# scheme_EasyEDA.net
KiCad netlist of a schematic drawn in EasyEDA
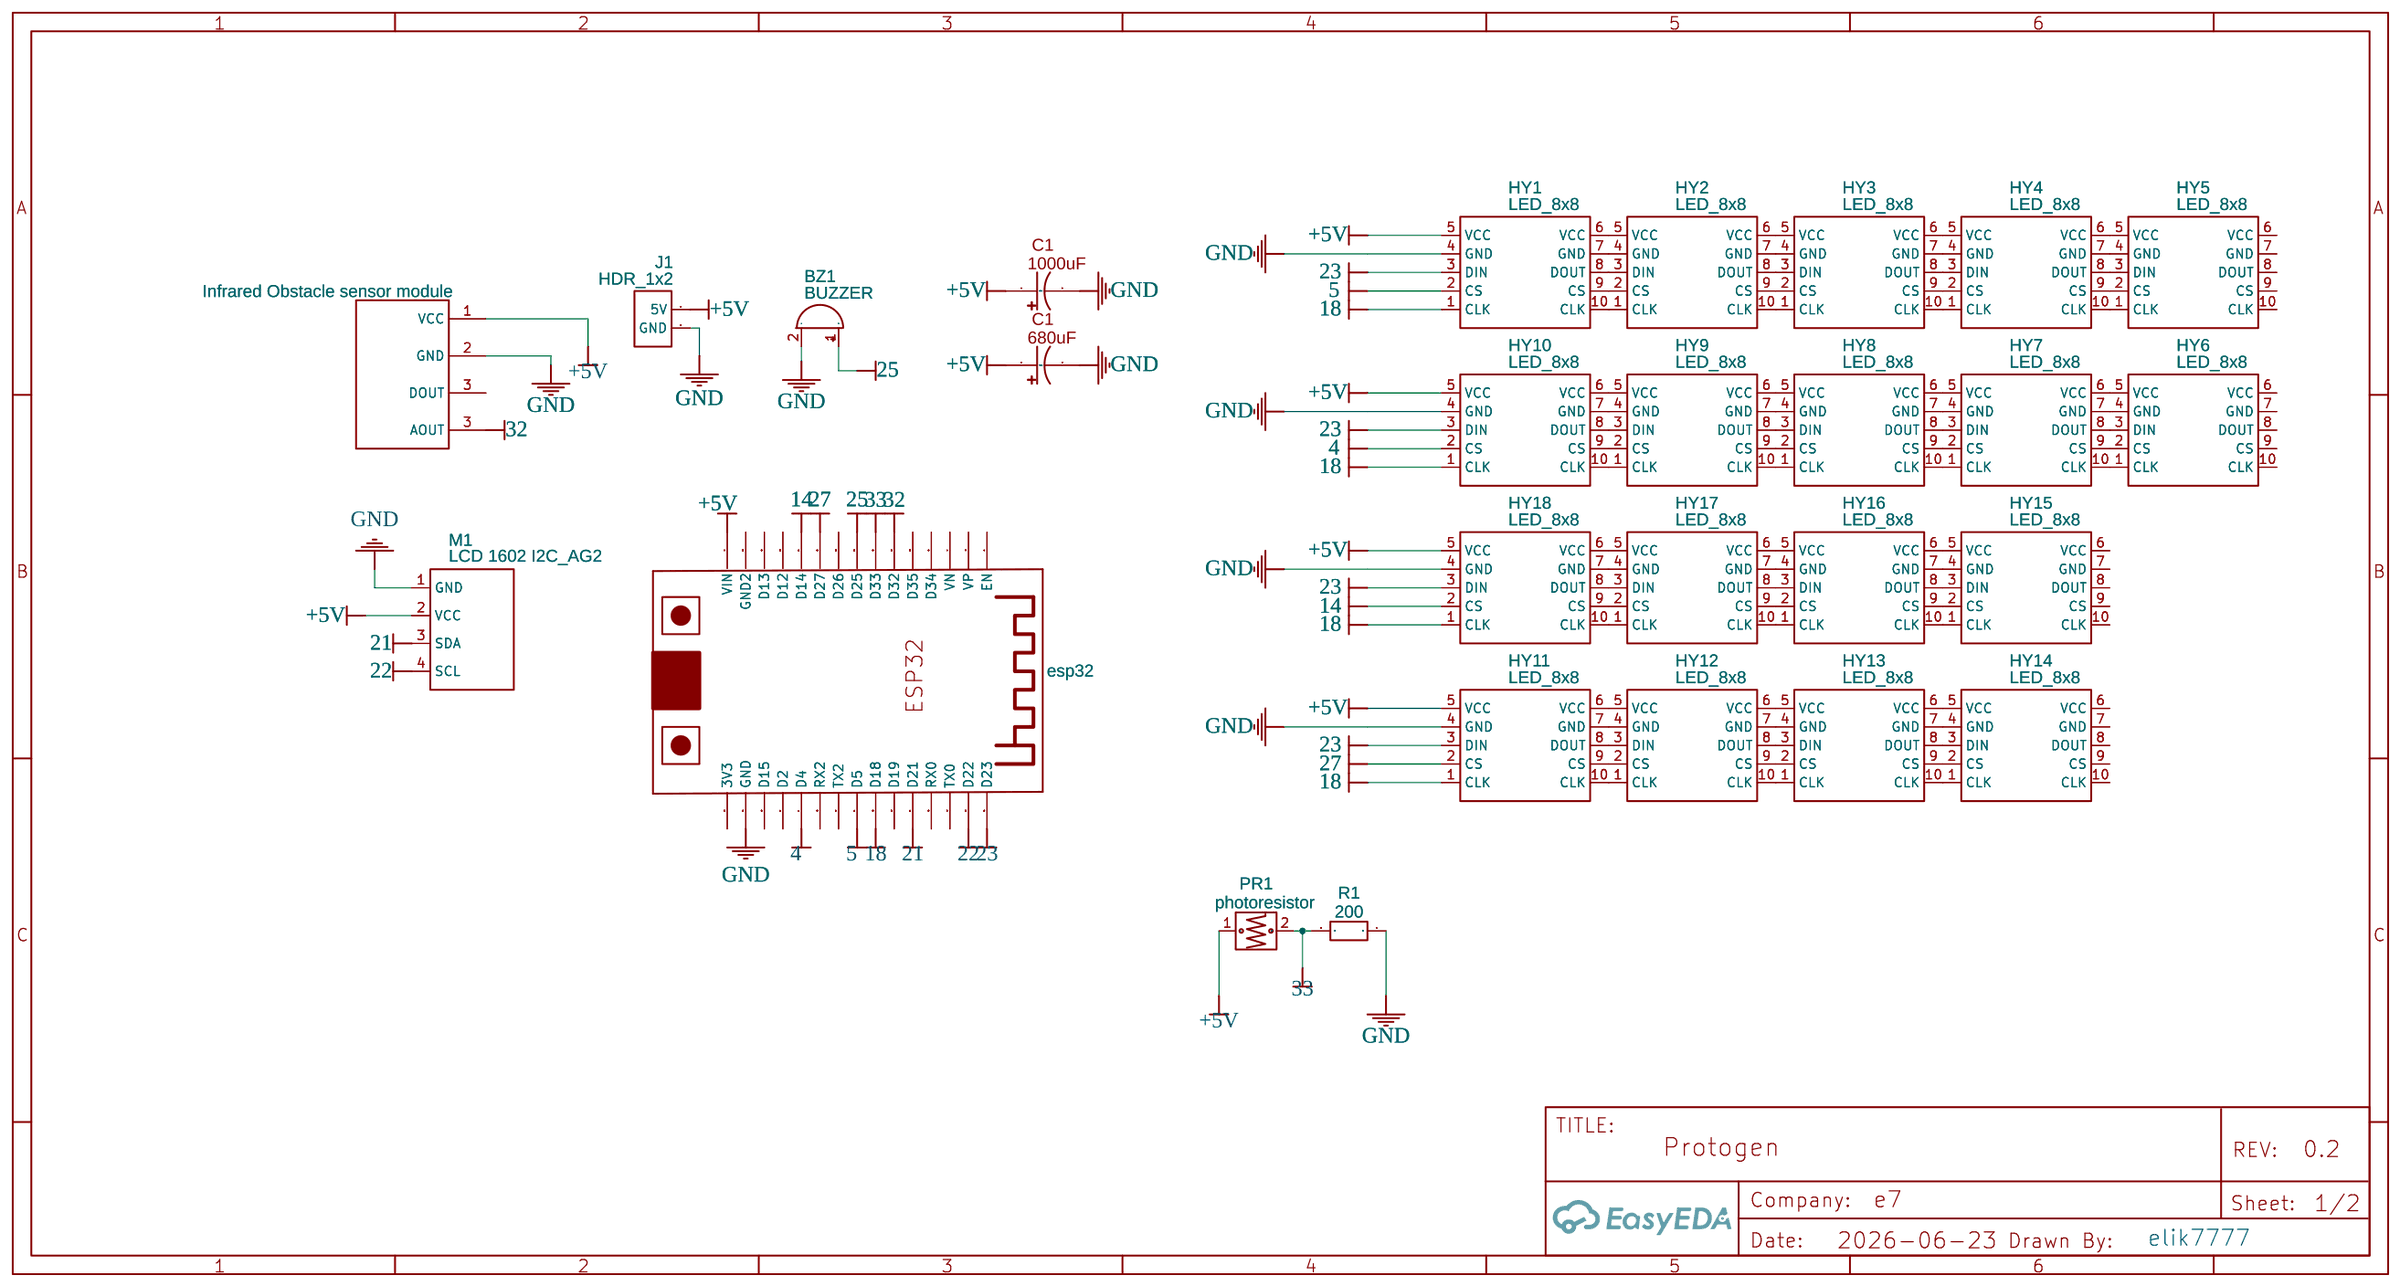
[diagram p0: schematic sheet]

(export (version "E")
  (design (tool "Eeschema 10.0.6"))
  (components
    (comp (ref "1") (value "esp32") (libsource (lib "") (part "ESP32-DEVKIT-V1-30PIN")))
    (comp (ref "BZ1") (value "BUZZER") (libsource (lib "") (part "DEVICE_BUZZER KU")))
    (comp (ref "HY1")
      (value "LED_8x8")
      (fields
        (field (name "Manufacturer Part") "32305941397 B")
        (field (name "Manufacturer") "Artillery 3C Store")
      )
      (libsource (lib "") (part "LED_8x8_MAX7219 cm"))
    )
    (comp (ref "HY2")
      (value "LED_8x8")
      (fields
        (field (name "Manufacturer Part") "32305941397 B")
        (field (name "Manufacturer") "Artillery 3C Store")
      )
      (libsource (lib "") (part "LED_8x8_MAX7219 cm"))
    )
    (comp (ref "HY3")
      (value "LED_8x8")
      (fields
        (field (name "Manufacturer Part") "32305941397 B")
        (field (name "Manufacturer") "Artillery 3C Store")
      )
      (libsource (lib "") (part "LED_8x8_MAX7219 cm"))
    )
    (comp (ref "HY4")
      (value "LED_8x8")
      (fields
        (field (name "Manufacturer Part") "32305941397 B")
        (field (name "Manufacturer") "Artillery 3C Store")
      )
      (libsource (lib "") (part "LED_8x8_MAX7219 cm"))
    )
    (comp (ref "HY5")
      (value "LED_8x8")
      (fields
        (field (name "Manufacturer Part") "32305941397 B")
        (field (name "Manufacturer") "Artillery 3C Store")
      )
      (libsource (lib "") (part "LED_8x8_MAX7219 cm"))
    )
    (comp (ref "HY6")
      (value "LED_8x8")
      (fields
        (field (name "Manufacturer Part") "32305941397 B")
        (field (name "Manufacturer") "Artillery 3C Store")
      )
      (libsource (lib "") (part "LED_8x8_MAX7219 cm"))
    )
    (comp (ref "HY7")
      (value "LED_8x8")
      (fields
        (field (name "Manufacturer Part") "32305941397 B")
        (field (name "Manufacturer") "Artillery 3C Store")
      )
      (libsource (lib "") (part "LED_8x8_MAX7219 cm"))
    )
    (comp (ref "HY8")
      (value "LED_8x8")
      (fields
        (field (name "Manufacturer Part") "32305941397 B")
        (field (name "Manufacturer") "Artillery 3C Store")
      )
      (libsource (lib "") (part "LED_8x8_MAX7219 cm"))
    )
    (comp (ref "HY9")
      (value "LED_8x8")
      (fields
        (field (name "Manufacturer Part") "32305941397 B")
        (field (name "Manufacturer") "Artillery 3C Store")
      )
      (libsource (lib "") (part "LED_8x8_MAX7219 cm"))
    )
    (comp (ref "HY10")
      (value "LED_8x8")
      (fields
        (field (name "Manufacturer Part") "32305941397 B")
        (field (name "Manufacturer") "Artillery 3C Store")
      )
      (libsource (lib "") (part "LED_8x8_MAX7219 cm"))
    )
    (comp (ref "HY11")
      (value "LED_8x8")
      (fields
        (field (name "Manufacturer Part") "32305941397 B")
        (field (name "Manufacturer") "Artillery 3C Store")
      )
      (libsource (lib "") (part "LED_8x8_MAX7219 cm"))
    )
    (comp (ref "HY12")
      (value "LED_8x8")
      (fields
        (field (name "Manufacturer Part") "32305941397 B")
        (field (name "Manufacturer") "Artillery 3C Store")
      )
      (libsource (lib "") (part "LED_8x8_MAX7219 cm"))
    )
    (comp (ref "HY13")
      (value "LED_8x8")
      (fields
        (field (name "Manufacturer Part") "32305941397 B")
        (field (name "Manufacturer") "Artillery 3C Store")
      )
      (libsource (lib "") (part "LED_8x8_MAX7219 cm"))
    )
    (comp (ref "HY14")
      (value "LED_8x8")
      (fields
        (field (name "Manufacturer Part") "32305941397 B")
        (field (name "Manufacturer") "Artillery 3C Store")
      )
      (libsource (lib "") (part "LED_8x8_MAX7219 cm"))
    )
    (comp (ref "HY15")
      (value "LED_8x8")
      (fields
        (field (name "Manufacturer Part") "32305941397 B")
        (field (name "Manufacturer") "Artillery 3C Store")
      )
      (libsource (lib "") (part "LED_8x8_MAX7219 cm"))
    )
    (comp (ref "HY16")
      (value "LED_8x8")
      (fields
        (field (name "Manufacturer Part") "32305941397 B")
        (field (name "Manufacturer") "Artillery 3C Store")
      )
      (libsource (lib "") (part "LED_8x8_MAX7219 cm"))
    )
    (comp (ref "HY17")
      (value "LED_8x8")
      (fields
        (field (name "Manufacturer Part") "32305941397 B")
        (field (name "Manufacturer") "Artillery 3C Store")
      )
      (libsource (lib "") (part "LED_8x8_MAX7219 cm"))
    )
    (comp (ref "HY18")
      (value "LED_8x8")
      (fields
        (field (name "Manufacturer Part") "32305941397 B")
        (field (name "Manufacturer") "Artillery 3C Store")
      )
      (libsource (lib "") (part "LED_8x8_MAX7219 cm"))
    )
    (comp (ref "J1") (value "HDR_1x2") (libsource (lib "") (part "HDR-M-2.54_1x2")))
    (comp (ref "M1") (value "LCD 1602 I2C_AG2") (libsource (lib "") (part "LCD 1602 I2C_AG2")))
    (comp (ref "PR1") (value "photoresistor") (libsource (lib "") (part "photoresistor")))
    (comp (ref "R1") (value "200") (libsource (lib "") (part "R_AXIAL-0.3_EU")))
    (comp (ref "U1") (value "CAPACITOR") (libsource (lib "") (part "CAPACITOR_1")))
    (comp (ref "U2") (value "CAPACITOR") (libsource (lib "") (part "CAPACITOR")))
    (comp (ref "U3")
      (value "Infrared Obstacle sensor module")
      (libsource (lib "") (part "Infrared Obstacle sensor module"))
    )
  )
  (nets
    (net (code "1") (name "+5V") (class "Default")
      (node (ref "1") (pin "VIN") (pinfunction "VIN_VIN") (pintype "unspecified"))
      (node (ref "HY1") (pin "5") (pinfunction "VCC_5") (pintype "unspecified"))
      (node (ref "HY10") (pin "5") (pinfunction "VCC_5") (pintype "unspecified"))
      (node (ref "HY11") (pin "5") (pinfunction "VCC_5") (pintype "unspecified"))
      (node (ref "HY18") (pin "5") (pinfunction "VCC_5") (pintype "unspecified"))
      (node (ref "J1") (pin "1") (pinfunction "5V_1") (pintype "unspecified"))
      (node (ref "M1") (pin "2") (pinfunction "VCC_2") (pintype "unspecified"))
      (node (ref "PR1") (pin "1") (pinfunction "1_1") (pintype "unspecified"))
      (node (ref "U1") (pin "1") (pinfunction "1_1") (pintype "unspecified"))
      (node (ref "U2") (pin "1") (pinfunction "1_1") (pintype "unspecified"))
      (node (ref "U3") (pin "1") (pinfunction "VCC_1") (pintype "unspecified"))
    )
    (net (code "2") (name "4") (class "Default")
      (node (ref "1") (pin "D4") (pinfunction "D4_D4") (pintype "unspecified"))
      (node (ref "HY10") (pin "2") (pinfunction "CS_2") (pintype "unspecified"))
    )
    (net (code "3") (name "5") (class "Default")
      (node (ref "1") (pin "D5") (pinfunction "D5_D5") (pintype "unspecified"))
      (node (ref "HY1") (pin "2") (pinfunction "CS_2") (pintype "unspecified"))
    )
    (net (code "4") (name "14") (class "Default")
      (node (ref "1") (pin "D14") (pinfunction "D14_D14") (pintype "unspecified"))
      (node (ref "HY18") (pin "2") (pinfunction "CS_2") (pintype "unspecified"))
    )
    (net (code "5") (name "18") (class "Default")
      (node (ref "1") (pin "D18") (pinfunction "D18_D18") (pintype "unspecified"))
      (node (ref "HY1") (pin "1") (pinfunction "CLK_1") (pintype "unspecified"))
      (node (ref "HY10") (pin "1") (pinfunction "CLK_1") (pintype "unspecified"))
      (node (ref "HY11") (pin "1") (pinfunction "CLK_1") (pintype "unspecified"))
      (node (ref "HY18") (pin "1") (pinfunction "CLK_1") (pintype "unspecified"))
    )
    (net (code "6") (name "21") (class "Default")
      (node (ref "1") (pin "D21") (pinfunction "D21_D21") (pintype "unspecified"))
      (node (ref "M1") (pin "3") (pinfunction "SDA_3") (pintype "unspecified"))
    )
    (net (code "7") (name "22") (class "Default")
      (node (ref "1") (pin "D22") (pinfunction "D22_D22") (pintype "unspecified"))
      (node (ref "M1") (pin "4") (pinfunction "SCL_4") (pintype "unspecified"))
    )
    (net (code "8") (name "23") (class "Default")
      (node (ref "1") (pin "D23") (pinfunction "D23_D23") (pintype "unspecified"))
      (node (ref "HY1") (pin "3") (pinfunction "DIN_3") (pintype "unspecified"))
      (node (ref "HY10") (pin "3") (pinfunction "DIN_3") (pintype "unspecified"))
      (node (ref "HY11") (pin "3") (pinfunction "DIN_3") (pintype "unspecified"))
      (node (ref "HY18") (pin "3") (pinfunction "DIN_3") (pintype "unspecified"))
    )
    (net (code "9") (name "25") (class "Default")
      (node (ref "1") (pin "D25") (pinfunction "D25_D25") (pintype "unspecified"))
      (node (ref "BZ1") (pin "1") (pinfunction "+_1") (pintype "unspecified"))
    )
    (net (code "10") (name "27") (class "Default")
      (node (ref "1") (pin "D27") (pinfunction "D27_D27") (pintype "unspecified"))
      (node (ref "HY11") (pin "2") (pinfunction "CS_2") (pintype "unspecified"))
    )
    (net (code "11") (name "32") (class "Default")
      (node (ref "1") (pin "D32") (pinfunction "D32_D32") (pintype "unspecified"))
      (node (ref "U3") (pin "3") (pinfunction "AOUT_3") (pintype "unspecified"))
    )
    (net (code "12") (name "33") (class "Default")
      (node (ref "1") (pin "D33") (pinfunction "D33_D33") (pintype "unspecified"))
      (node (ref "PR1") (pin "2") (pinfunction "2_2") (pintype "unspecified"))
      (node (ref "R1") (pin "2") (pinfunction "2_2") (pintype "unspecified"))
    )
    (net (code "13") (name "GND") (class "Default")
      (node (ref "1") (pin "GND") (pinfunction "GND_GND") (pintype "unspecified"))
      (node (ref "BZ1") (pin "2") (pinfunction "-_2") (pintype "unspecified"))
      (node (ref "HY1") (pin "4") (pinfunction "GND_4") (pintype "unspecified"))
      (node (ref "HY10") (pin "4") (pinfunction "GND_4") (pintype "unspecified"))
      (node (ref "HY11") (pin "4") (pinfunction "GND_4") (pintype "unspecified"))
      (node (ref "HY18") (pin "4") (pinfunction "GND_4") (pintype "unspecified"))
      (node (ref "J1") (pin "2") (pinfunction "GND_2") (pintype "unspecified"))
      (node (ref "M1") (pin "1") (pinfunction "GND_1") (pintype "unspecified"))
      (node (ref "R1") (pin "1") (pinfunction "1_1") (pintype "unspecified"))
      (node (ref "U1") (pin "2") (pinfunction "2_2") (pintype "unspecified"))
      (node (ref "U2") (pin "2") (pinfunction "2_2") (pintype "unspecified"))
      (node (ref "U3") (pin "2") (pinfunction "GND_2") (pintype "unspecified"))
    )
    (net (code "14") (name "Net-(HY1-CLK-Pad10)") (class "Default")
      (node (ref "HY1") (pin "10") (pinfunction "CLK_10") (pintype "unspecified"))
      (node (ref "HY2") (pin "1") (pinfunction "CLK_1") (pintype "unspecified"))
    )
    (net (code "15") (name "Net-(HY1-CS-Pad9)") (class "Default")
      (node (ref "HY1") (pin "9") (pinfunction "CS_9") (pintype "unspecified"))
      (node (ref "HY2") (pin "2") (pinfunction "CS_2") (pintype "unspecified"))
    )
    (net (code "16") (name "Net-(HY1-DOUT)") (class "Default")
      (node (ref "HY1") (pin "8") (pinfunction "DOUT_8") (pintype "unspecified"))
      (node (ref "HY2") (pin "3") (pinfunction "DIN_3") (pintype "unspecified"))
    )
    (net (code "17") (name "Net-(HY1-GND-Pad7)") (class "Default")
      (node (ref "HY1") (pin "7") (pinfunction "GND_7") (pintype "unspecified"))
      (node (ref "HY2") (pin "4") (pinfunction "GND_4") (pintype "unspecified"))
    )
    (net (code "18") (name "Net-(HY1-VCC-Pad6)") (class "Default")
      (node (ref "HY1") (pin "6") (pinfunction "VCC_6") (pintype "unspecified"))
      (node (ref "HY2") (pin "5") (pinfunction "VCC_5") (pintype "unspecified"))
    )
    (net (code "19") (name "Net-(HY2-CLK-Pad10)") (class "Default")
      (node (ref "HY2") (pin "10") (pinfunction "CLK_10") (pintype "unspecified"))
      (node (ref "HY3") (pin "1") (pinfunction "CLK_1") (pintype "unspecified"))
    )
    (net (code "20") (name "Net-(HY2-CS-Pad9)") (class "Default")
      (node (ref "HY2") (pin "9") (pinfunction "CS_9") (pintype "unspecified"))
      (node (ref "HY3") (pin "2") (pinfunction "CS_2") (pintype "unspecified"))
    )
    (net (code "21") (name "Net-(HY2-DOUT)") (class "Default")
      (node (ref "HY2") (pin "8") (pinfunction "DOUT_8") (pintype "unspecified"))
      (node (ref "HY3") (pin "3") (pinfunction "DIN_3") (pintype "unspecified"))
    )
    (net (code "22") (name "Net-(HY2-GND-Pad7)") (class "Default")
      (node (ref "HY2") (pin "7") (pinfunction "GND_7") (pintype "unspecified"))
      (node (ref "HY3") (pin "4") (pinfunction "GND_4") (pintype "unspecified"))
    )
    (net (code "23") (name "Net-(HY2-VCC-Pad6)") (class "Default")
      (node (ref "HY2") (pin "6") (pinfunction "VCC_6") (pintype "unspecified"))
      (node (ref "HY3") (pin "5") (pinfunction "VCC_5") (pintype "unspecified"))
    )
    (net (code "24") (name "Net-(HY3-CLK-Pad10)") (class "Default")
      (node (ref "HY3") (pin "10") (pinfunction "CLK_10") (pintype "unspecified"))
      (node (ref "HY4") (pin "1") (pinfunction "CLK_1") (pintype "unspecified"))
    )
    (net (code "25") (name "Net-(HY3-CS-Pad9)") (class "Default")
      (node (ref "HY3") (pin "9") (pinfunction "CS_9") (pintype "unspecified"))
      (node (ref "HY4") (pin "2") (pinfunction "CS_2") (pintype "unspecified"))
    )
    (net (code "26") (name "Net-(HY3-DOUT)") (class "Default")
      (node (ref "HY3") (pin "8") (pinfunction "DOUT_8") (pintype "unspecified"))
      (node (ref "HY4") (pin "3") (pinfunction "DIN_3") (pintype "unspecified"))
    )
    (net (code "27") (name "Net-(HY3-GND-Pad7)") (class "Default")
      (node (ref "HY3") (pin "7") (pinfunction "GND_7") (pintype "unspecified"))
      (node (ref "HY4") (pin "4") (pinfunction "GND_4") (pintype "unspecified"))
    )
    (net (code "28") (name "Net-(HY3-VCC-Pad6)") (class "Default")
      (node (ref "HY3") (pin "6") (pinfunction "VCC_6") (pintype "unspecified"))
      (node (ref "HY4") (pin "5") (pinfunction "VCC_5") (pintype "unspecified"))
    )
    (net (code "29") (name "Net-(HY4-CLK-Pad10)") (class "Default")
      (node (ref "HY4") (pin "10") (pinfunction "CLK_10") (pintype "unspecified"))
      (node (ref "HY5") (pin "1") (pinfunction "CLK_1") (pintype "unspecified"))
    )
    (net (code "30") (name "Net-(HY4-CS-Pad9)") (class "Default")
      (node (ref "HY4") (pin "9") (pinfunction "CS_9") (pintype "unspecified"))
      (node (ref "HY5") (pin "2") (pinfunction "CS_2") (pintype "unspecified"))
    )
    (net (code "31") (name "Net-(HY4-DOUT)") (class "Default")
      (node (ref "HY4") (pin "8") (pinfunction "DOUT_8") (pintype "unspecified"))
      (node (ref "HY5") (pin "3") (pinfunction "DIN_3") (pintype "unspecified"))
    )
    (net (code "32") (name "Net-(HY4-GND-Pad7)") (class "Default")
      (node (ref "HY4") (pin "7") (pinfunction "GND_7") (pintype "unspecified"))
      (node (ref "HY5") (pin "4") (pinfunction "GND_4") (pintype "unspecified"))
    )
    (net (code "33") (name "Net-(HY4-VCC-Pad6)") (class "Default")
      (node (ref "HY4") (pin "6") (pinfunction "VCC_6") (pintype "unspecified"))
      (node (ref "HY5") (pin "5") (pinfunction "VCC_5") (pintype "unspecified"))
    )
    (net (code "34") (name "Net-(HY6-CLK-Pad1)") (class "Default")
      (node (ref "HY6") (pin "1") (pinfunction "CLK_1") (pintype "unspecified"))
      (node (ref "HY7") (pin "10") (pinfunction "CLK_10") (pintype "unspecified"))
    )
    (net (code "35") (name "Net-(HY6-CS-Pad2)") (class "Default")
      (node (ref "HY6") (pin "2") (pinfunction "CS_2") (pintype "unspecified"))
      (node (ref "HY7") (pin "9") (pinfunction "CS_9") (pintype "unspecified"))
    )
    (net (code "36") (name "Net-(HY6-DIN)") (class "Default")
      (node (ref "HY6") (pin "3") (pinfunction "DIN_3") (pintype "unspecified"))
      (node (ref "HY7") (pin "8") (pinfunction "DOUT_8") (pintype "unspecified"))
    )
    (net (code "37") (name "Net-(HY6-GND-Pad4)") (class "Default")
      (node (ref "HY6") (pin "4") (pinfunction "GND_4") (pintype "unspecified"))
      (node (ref "HY7") (pin "7") (pinfunction "GND_7") (pintype "unspecified"))
    )
    (net (code "38") (name "Net-(HY6-VCC-Pad5)") (class "Default")
      (node (ref "HY6") (pin "5") (pinfunction "VCC_5") (pintype "unspecified"))
      (node (ref "HY7") (pin "6") (pinfunction "VCC_6") (pintype "unspecified"))
    )
    (net (code "39") (name "Net-(HY7-CLK-Pad1)") (class "Default")
      (node (ref "HY7") (pin "1") (pinfunction "CLK_1") (pintype "unspecified"))
      (node (ref "HY8") (pin "10") (pinfunction "CLK_10") (pintype "unspecified"))
    )
    (net (code "40") (name "Net-(HY7-CS-Pad2)") (class "Default")
      (node (ref "HY7") (pin "2") (pinfunction "CS_2") (pintype "unspecified"))
      (node (ref "HY8") (pin "9") (pinfunction "CS_9") (pintype "unspecified"))
    )
    (net (code "41") (name "Net-(HY7-DIN)") (class "Default")
      (node (ref "HY7") (pin "3") (pinfunction "DIN_3") (pintype "unspecified"))
      (node (ref "HY8") (pin "8") (pinfunction "DOUT_8") (pintype "unspecified"))
    )
    (net (code "42") (name "Net-(HY7-GND-Pad4)") (class "Default")
      (node (ref "HY7") (pin "4") (pinfunction "GND_4") (pintype "unspecified"))
      (node (ref "HY8") (pin "7") (pinfunction "GND_7") (pintype "unspecified"))
    )
    (net (code "43") (name "Net-(HY7-VCC-Pad5)") (class "Default")
      (node (ref "HY7") (pin "5") (pinfunction "VCC_5") (pintype "unspecified"))
      (node (ref "HY8") (pin "6") (pinfunction "VCC_6") (pintype "unspecified"))
    )
    (net (code "44") (name "Net-(HY8-CLK-Pad1)") (class "Default")
      (node (ref "HY8") (pin "1") (pinfunction "CLK_1") (pintype "unspecified"))
      (node (ref "HY9") (pin "10") (pinfunction "CLK_10") (pintype "unspecified"))
    )
    (net (code "45") (name "Net-(HY8-CS-Pad2)") (class "Default")
      (node (ref "HY8") (pin "2") (pinfunction "CS_2") (pintype "unspecified"))
      (node (ref "HY9") (pin "9") (pinfunction "CS_9") (pintype "unspecified"))
    )
    (net (code "46") (name "Net-(HY8-DIN)") (class "Default")
      (node (ref "HY8") (pin "3") (pinfunction "DIN_3") (pintype "unspecified"))
      (node (ref "HY9") (pin "8") (pinfunction "DOUT_8") (pintype "unspecified"))
    )
    (net (code "47") (name "Net-(HY8-GND-Pad4)") (class "Default")
      (node (ref "HY8") (pin "4") (pinfunction "GND_4") (pintype "unspecified"))
      (node (ref "HY9") (pin "7") (pinfunction "GND_7") (pintype "unspecified"))
    )
    (net (code "48") (name "Net-(HY8-VCC-Pad5)") (class "Default")
      (node (ref "HY8") (pin "5") (pinfunction "VCC_5") (pintype "unspecified"))
      (node (ref "HY9") (pin "6") (pinfunction "VCC_6") (pintype "unspecified"))
    )
    (net (code "49") (name "Net-(HY10-CLK-Pad10)") (class "Default")
      (node (ref "HY10") (pin "10") (pinfunction "CLK_10") (pintype "unspecified"))
      (node (ref "HY9") (pin "1") (pinfunction "CLK_1") (pintype "unspecified"))
    )
    (net (code "50") (name "Net-(HY10-CS-Pad9)") (class "Default")
      (node (ref "HY10") (pin "9") (pinfunction "CS_9") (pintype "unspecified"))
      (node (ref "HY9") (pin "2") (pinfunction "CS_2") (pintype "unspecified"))
    )
    (net (code "51") (name "Net-(HY10-DOUT)") (class "Default")
      (node (ref "HY10") (pin "8") (pinfunction "DOUT_8") (pintype "unspecified"))
      (node (ref "HY9") (pin "3") (pinfunction "DIN_3") (pintype "unspecified"))
    )
    (net (code "52") (name "Net-(HY10-GND-Pad7)") (class "Default")
      (node (ref "HY10") (pin "7") (pinfunction "GND_7") (pintype "unspecified"))
      (node (ref "HY9") (pin "4") (pinfunction "GND_4") (pintype "unspecified"))
    )
    (net (code "53") (name "Net-(HY10-VCC-Pad6)") (class "Default")
      (node (ref "HY10") (pin "6") (pinfunction "VCC_6") (pintype "unspecified"))
      (node (ref "HY9") (pin "5") (pinfunction "VCC_5") (pintype "unspecified"))
    )
    (net (code "54") (name "Net-(HY11-CLK-Pad10)") (class "Default")
      (node (ref "HY11") (pin "10") (pinfunction "CLK_10") (pintype "unspecified"))
      (node (ref "HY12") (pin "1") (pinfunction "CLK_1") (pintype "unspecified"))
    )
    (net (code "55") (name "Net-(HY11-CS-Pad9)") (class "Default")
      (node (ref "HY11") (pin "9") (pinfunction "CS_9") (pintype "unspecified"))
      (node (ref "HY12") (pin "2") (pinfunction "CS_2") (pintype "unspecified"))
    )
    (net (code "56") (name "Net-(HY11-DOUT)") (class "Default")
      (node (ref "HY11") (pin "8") (pinfunction "DOUT_8") (pintype "unspecified"))
      (node (ref "HY12") (pin "3") (pinfunction "DIN_3") (pintype "unspecified"))
    )
    (net (code "57") (name "Net-(HY11-GND-Pad7)") (class "Default")
      (node (ref "HY11") (pin "7") (pinfunction "GND_7") (pintype "unspecified"))
      (node (ref "HY12") (pin "4") (pinfunction "GND_4") (pintype "unspecified"))
    )
    (net (code "58") (name "Net-(HY11-VCC-Pad6)") (class "Default")
      (node (ref "HY11") (pin "6") (pinfunction "VCC_6") (pintype "unspecified"))
      (node (ref "HY12") (pin "5") (pinfunction "VCC_5") (pintype "unspecified"))
    )
    (net (code "59") (name "Net-(HY12-CLK-Pad10)") (class "Default")
      (node (ref "HY12") (pin "10") (pinfunction "CLK_10") (pintype "unspecified"))
      (node (ref "HY13") (pin "1") (pinfunction "CLK_1") (pintype "unspecified"))
    )
    (net (code "60") (name "Net-(HY12-CS-Pad9)") (class "Default")
      (node (ref "HY12") (pin "9") (pinfunction "CS_9") (pintype "unspecified"))
      (node (ref "HY13") (pin "2") (pinfunction "CS_2") (pintype "unspecified"))
    )
    (net (code "61") (name "Net-(HY12-DOUT)") (class "Default")
      (node (ref "HY12") (pin "8") (pinfunction "DOUT_8") (pintype "unspecified"))
      (node (ref "HY13") (pin "3") (pinfunction "DIN_3") (pintype "unspecified"))
    )
    (net (code "62") (name "Net-(HY12-GND-Pad7)") (class "Default")
      (node (ref "HY12") (pin "7") (pinfunction "GND_7") (pintype "unspecified"))
      (node (ref "HY13") (pin "4") (pinfunction "GND_4") (pintype "unspecified"))
    )
    (net (code "63") (name "Net-(HY12-VCC-Pad6)") (class "Default")
      (node (ref "HY12") (pin "6") (pinfunction "VCC_6") (pintype "unspecified"))
      (node (ref "HY13") (pin "5") (pinfunction "VCC_5") (pintype "unspecified"))
    )
    (net (code "64") (name "Net-(HY13-CLK-Pad10)") (class "Default")
      (node (ref "HY13") (pin "10") (pinfunction "CLK_10") (pintype "unspecified"))
      (node (ref "HY14") (pin "1") (pinfunction "CLK_1") (pintype "unspecified"))
    )
    (net (code "65") (name "Net-(HY13-CS-Pad9)") (class "Default")
      (node (ref "HY13") (pin "9") (pinfunction "CS_9") (pintype "unspecified"))
      (node (ref "HY14") (pin "2") (pinfunction "CS_2") (pintype "unspecified"))
    )
    (net (code "66") (name "Net-(HY13-DOUT)") (class "Default")
      (node (ref "HY13") (pin "8") (pinfunction "DOUT_8") (pintype "unspecified"))
      (node (ref "HY14") (pin "3") (pinfunction "DIN_3") (pintype "unspecified"))
    )
    (net (code "67") (name "Net-(HY13-GND-Pad7)") (class "Default")
      (node (ref "HY13") (pin "7") (pinfunction "GND_7") (pintype "unspecified"))
      (node (ref "HY14") (pin "4") (pinfunction "GND_4") (pintype "unspecified"))
    )
    (net (code "68") (name "Net-(HY13-VCC-Pad6)") (class "Default")
      (node (ref "HY13") (pin "6") (pinfunction "VCC_6") (pintype "unspecified"))
      (node (ref "HY14") (pin "5") (pinfunction "VCC_5") (pintype "unspecified"))
    )
    (net (code "69") (name "Net-(HY15-CLK-Pad1)") (class "Default")
      (node (ref "HY15") (pin "1") (pinfunction "CLK_1") (pintype "unspecified"))
      (node (ref "HY16") (pin "10") (pinfunction "CLK_10") (pintype "unspecified"))
    )
    (net (code "70") (name "Net-(HY15-CS-Pad2)") (class "Default")
      (node (ref "HY15") (pin "2") (pinfunction "CS_2") (pintype "unspecified"))
      (node (ref "HY16") (pin "9") (pinfunction "CS_9") (pintype "unspecified"))
    )
    (net (code "71") (name "Net-(HY15-DIN)") (class "Default")
      (node (ref "HY15") (pin "3") (pinfunction "DIN_3") (pintype "unspecified"))
      (node (ref "HY16") (pin "8") (pinfunction "DOUT_8") (pintype "unspecified"))
    )
    (net (code "72") (name "Net-(HY15-GND-Pad4)") (class "Default")
      (node (ref "HY15") (pin "4") (pinfunction "GND_4") (pintype "unspecified"))
      (node (ref "HY16") (pin "7") (pinfunction "GND_7") (pintype "unspecified"))
    )
    (net (code "73") (name "Net-(HY15-VCC-Pad5)") (class "Default")
      (node (ref "HY15") (pin "5") (pinfunction "VCC_5") (pintype "unspecified"))
      (node (ref "HY16") (pin "6") (pinfunction "VCC_6") (pintype "unspecified"))
    )
    (net (code "74") (name "Net-(HY16-CLK-Pad1)") (class "Default")
      (node (ref "HY16") (pin "1") (pinfunction "CLK_1") (pintype "unspecified"))
      (node (ref "HY17") (pin "10") (pinfunction "CLK_10") (pintype "unspecified"))
    )
    (net (code "75") (name "Net-(HY16-CS-Pad2)") (class "Default")
      (node (ref "HY16") (pin "2") (pinfunction "CS_2") (pintype "unspecified"))
      (node (ref "HY17") (pin "9") (pinfunction "CS_9") (pintype "unspecified"))
    )
    (net (code "76") (name "Net-(HY16-DIN)") (class "Default")
      (node (ref "HY16") (pin "3") (pinfunction "DIN_3") (pintype "unspecified"))
      (node (ref "HY17") (pin "8") (pinfunction "DOUT_8") (pintype "unspecified"))
    )
    (net (code "77") (name "Net-(HY16-GND-Pad4)") (class "Default")
      (node (ref "HY16") (pin "4") (pinfunction "GND_4") (pintype "unspecified"))
      (node (ref "HY17") (pin "7") (pinfunction "GND_7") (pintype "unspecified"))
    )
    (net (code "78") (name "Net-(HY16-VCC-Pad5)") (class "Default")
      (node (ref "HY16") (pin "5") (pinfunction "VCC_5") (pintype "unspecified"))
      (node (ref "HY17") (pin "6") (pinfunction "VCC_6") (pintype "unspecified"))
    )
    (net (code "79") (name "Net-(HY17-CLK-Pad1)") (class "Default")
      (node (ref "HY17") (pin "1") (pinfunction "CLK_1") (pintype "unspecified"))
      (node (ref "HY18") (pin "10") (pinfunction "CLK_10") (pintype "unspecified"))
    )
    (net (code "80") (name "Net-(HY17-CS-Pad2)") (class "Default")
      (node (ref "HY17") (pin "2") (pinfunction "CS_2") (pintype "unspecified"))
      (node (ref "HY18") (pin "9") (pinfunction "CS_9") (pintype "unspecified"))
    )
    (net (code "81") (name "Net-(HY17-DIN)") (class "Default")
      (node (ref "HY17") (pin "3") (pinfunction "DIN_3") (pintype "unspecified"))
      (node (ref "HY18") (pin "8") (pinfunction "DOUT_8") (pintype "unspecified"))
    )
    (net (code "82") (name "Net-(HY17-GND-Pad4)") (class "Default")
      (node (ref "HY17") (pin "4") (pinfunction "GND_4") (pintype "unspecified"))
      (node (ref "HY18") (pin "7") (pinfunction "GND_7") (pintype "unspecified"))
    )
    (net (code "83") (name "Net-(HY17-VCC-Pad5)") (class "Default")
      (node (ref "HY17") (pin "5") (pinfunction "VCC_5") (pintype "unspecified"))
      (node (ref "HY18") (pin "6") (pinfunction "VCC_6") (pintype "unspecified"))
    )
    (net (code "84") (name "unconnected-(1-Pad3V3)") (class "Default")
      (node (ref "1") (pin "3V3") (pinfunction "3V3_3V3") (pintype "unspecified"))
    )
    (net (code "85") (name "unconnected-(1-PadD2)") (class "Default")
      (node (ref "1") (pin "D2") (pinfunction "D2_D2") (pintype "unspecified"))
    )
    (net (code "86") (name "unconnected-(1-PadD12)") (class "Default")
      (node (ref "1") (pin "D12") (pinfunction "D12_D12") (pintype "unspecified"))
    )
    (net (code "87") (name "unconnected-(1-PadD13)") (class "Default")
      (node (ref "1") (pin "D13") (pinfunction "D13_D13") (pintype "unspecified"))
    )
    (net (code "88") (name "unconnected-(1-PadD15)") (class "Default")
      (node (ref "1") (pin "D15") (pinfunction "D15_D15") (pintype "unspecified"))
    )
    (net (code "89") (name "unconnected-(1-PadD19)") (class "Default")
      (node (ref "1") (pin "D19") (pinfunction "D19_D19") (pintype "unspecified"))
    )
    (net (code "90") (name "unconnected-(1-PadD26)") (class "Default")
      (node (ref "1") (pin "D26") (pinfunction "D26_D26") (pintype "unspecified"))
    )
    (net (code "91") (name "unconnected-(1-PadD34)") (class "Default")
      (node (ref "1") (pin "D34") (pinfunction "D34_D34") (pintype "unspecified"))
    )
    (net (code "92") (name "unconnected-(1-PadD35)") (class "Default")
      (node (ref "1") (pin "D35") (pinfunction "D35_D35") (pintype "unspecified"))
    )
    (net (code "93") (name "unconnected-(1-PadEN)") (class "Default")
      (node (ref "1") (pin "EN") (pinfunction "EN_EN") (pintype "unspecified"))
    )
    (net (code "94") (name "unconnected-(1-PadGND2)") (class "Default")
      (node (ref "1") (pin "GND2") (pinfunction "GND2_GND2") (pintype "unspecified"))
    )
    (net (code "95") (name "unconnected-(1-PadRX0)") (class "Default")
      (node (ref "1") (pin "RX0") (pinfunction "RX0_RX0") (pintype "unspecified"))
    )
    (net (code "96") (name "unconnected-(1-PadRX2)") (class "Default")
      (node (ref "1") (pin "RX2") (pinfunction "RX2_RX2") (pintype "unspecified"))
    )
    (net (code "97") (name "unconnected-(1-PadTX0)") (class "Default")
      (node (ref "1") (pin "TX0") (pinfunction "TX0_TX0") (pintype "unspecified"))
    )
    (net (code "98") (name "unconnected-(1-PadTX2)") (class "Default")
      (node (ref "1") (pin "TX2") (pinfunction "TX2_TX2") (pintype "unspecified"))
    )
    (net (code "99") (name "unconnected-(1-PadVN)") (class "Default")
      (node (ref "1") (pin "VN") (pinfunction "VN_VN") (pintype "unspecified"))
    )
    (net (code "100") (name "unconnected-(1-PadVP)") (class "Default")
      (node (ref "1") (pin "VP") (pinfunction "VP_VP") (pintype "unspecified"))
    )
    (net (code "101") (name "unconnected-(HY5-CLK-Pad10)") (class "Default")
      (node (ref "HY5") (pin "10") (pinfunction "CLK_10") (pintype "unspecified"))
    )
    (net (code "102") (name "unconnected-(HY5-CS-Pad9)") (class "Default")
      (node (ref "HY5") (pin "9") (pinfunction "CS_9") (pintype "unspecified"))
    )
    (net (code "103") (name "unconnected-(HY5-DOUT-Pad8)") (class "Default")
      (node (ref "HY5") (pin "8") (pinfunction "DOUT_8") (pintype "unspecified"))
    )
    (net (code "104") (name "unconnected-(HY5-GND-Pad7)") (class "Default")
      (node (ref "HY5") (pin "7") (pinfunction "GND_7") (pintype "unspecified"))
    )
    (net (code "105") (name "unconnected-(HY5-VCC-Pad6)") (class "Default")
      (node (ref "HY5") (pin "6") (pinfunction "VCC_6") (pintype "unspecified"))
    )
    (net (code "106") (name "unconnected-(HY6-CLK-Pad10)") (class "Default")
      (node (ref "HY6") (pin "10") (pinfunction "CLK_10") (pintype "unspecified"))
    )
    (net (code "107") (name "unconnected-(HY6-CS-Pad9)") (class "Default")
      (node (ref "HY6") (pin "9") (pinfunction "CS_9") (pintype "unspecified"))
    )
    (net (code "108") (name "unconnected-(HY6-DOUT-Pad8)") (class "Default")
      (node (ref "HY6") (pin "8") (pinfunction "DOUT_8") (pintype "unspecified"))
    )
    (net (code "109") (name "unconnected-(HY6-GND-Pad7)") (class "Default")
      (node (ref "HY6") (pin "7") (pinfunction "GND_7") (pintype "unspecified"))
    )
    (net (code "110") (name "unconnected-(HY6-VCC-Pad6)") (class "Default")
      (node (ref "HY6") (pin "6") (pinfunction "VCC_6") (pintype "unspecified"))
    )
    (net (code "111") (name "unconnected-(HY14-CLK-Pad10)") (class "Default")
      (node (ref "HY14") (pin "10") (pinfunction "CLK_10") (pintype "unspecified"))
    )
    (net (code "112") (name "unconnected-(HY14-CS-Pad9)") (class "Default")
      (node (ref "HY14") (pin "9") (pinfunction "CS_9") (pintype "unspecified"))
    )
    (net (code "113") (name "unconnected-(HY14-DOUT-Pad8)") (class "Default")
      (node (ref "HY14") (pin "8") (pinfunction "DOUT_8") (pintype "unspecified"))
    )
    (net (code "114") (name "unconnected-(HY14-GND-Pad7)") (class "Default")
      (node (ref "HY14") (pin "7") (pinfunction "GND_7") (pintype "unspecified"))
    )
    (net (code "115") (name "unconnected-(HY14-VCC-Pad6)") (class "Default")
      (node (ref "HY14") (pin "6") (pinfunction "VCC_6") (pintype "unspecified"))
    )
    (net (code "116") (name "unconnected-(HY15-CLK-Pad10)") (class "Default")
      (node (ref "HY15") (pin "10") (pinfunction "CLK_10") (pintype "unspecified"))
    )
    (net (code "117") (name "unconnected-(HY15-CS-Pad9)") (class "Default")
      (node (ref "HY15") (pin "9") (pinfunction "CS_9") (pintype "unspecified"))
    )
    (net (code "118") (name "unconnected-(HY15-DOUT-Pad8)") (class "Default")
      (node (ref "HY15") (pin "8") (pinfunction "DOUT_8") (pintype "unspecified"))
    )
    (net (code "119") (name "unconnected-(HY15-GND-Pad7)") (class "Default")
      (node (ref "HY15") (pin "7") (pinfunction "GND_7") (pintype "unspecified"))
    )
    (net (code "120") (name "unconnected-(HY15-VCC-Pad6)") (class "Default")
      (node (ref "HY15") (pin "6") (pinfunction "VCC_6") (pintype "unspecified"))
    )
    (net (code "121") (name "unconnected-(U3-DOUT-Pad3)") (class "Default")
      (node (ref "U3") (pin "3") (pinfunction "DOUT_3") (pintype "unspecified"))
    )
  )
)
